# PAL3579.net
KiCad netlist of a schematic drawn in EAGLE
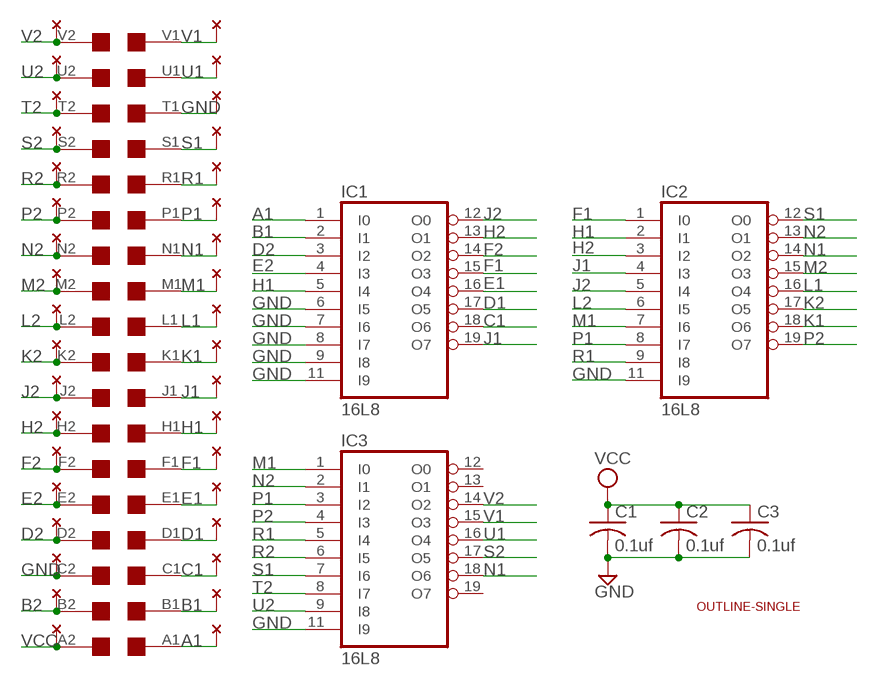
[diagram p0: schematic, sheet 1]

(export (version "E")
  (design (tool "Eeschema 10.0.6"))
  (components
    (comp (ref "C1")
      (value "0.1uf")
      (footprint "eagle-import:C050-025X075")
      (libsource (lib "eagle-import") (part "C-US050-025X075"))
    )
    (comp (ref "C2")
      (value "0.1uf")
      (footprint "eagle-import:C050-025X075")
      (libsource (lib "eagle-import") (part "C-US050-025X075"))
    )
    (comp (ref "C3")
      (value "0.1uf")
      (footprint "eagle-import:C050-025X075")
      (libsource (lib "eagle-import") (part "C-US050-025X075"))
    )
    (comp (ref "IC1")
      (value "16L8")
      (footprint "eagle-import:DIL20")
      (fields (field (name "MF") "TEXAS INSTRUMENTS") (field (name "MPN") "TIBPAL16L8-7CN"))
      (libsource (lib "eagle-import") (part "16L8"))
    )
    (comp (ref "IC2")
      (value "16L8")
      (footprint "eagle-import:DIL20")
      (fields (field (name "MF") "TEXAS INSTRUMENTS") (field (name "MPN") "TIBPAL16L8-7CN"))
      (libsource (lib "eagle-import") (part "16L8"))
    )
    (comp (ref "IC3")
      (value "16L8")
      (footprint "eagle-import:DIL20")
      (fields (field (name "MF") "TEXAS INSTRUMENTS") (field (name "MPN") "TIBPAL16L8-7CN"))
      (libsource (lib "eagle-import") (part "16L8"))
    )
    (comp (ref "U$1")
      (value "EDGE-2CONNECTOR")
      (footprint "eagle-import:EDGE-CON2")
      (libsource (lib "eagle-import") (part "EDGE-2CONNECTOR"))
    )
    (comp (ref "U$2")
      (value "OUTLINE-SINGLE")
      (footprint "eagle-import:SINGLE")
      (libsource (lib "eagle-import") (part "OUTLINE-SINGLE"))
    )
    (comp (ref "U$4")
      (value "THRU-HOLE2A")
      (footprint "eagle-import:THRU-HOLEA")
      (libsource (lib "eagle-import") (part "THRU-HOLE2A"))
    )
  )
  (nets
    (net (code "1") (name "/A1") (class "Default")
      (node (ref "IC1") (pin "1") (pinfunction "I0_1") (pintype "input"))
      (node (ref "U$1") (pin "A1") (pinfunction "1_A1") (pintype "bidirectional"))
      (node (ref "U$4") (pin "A1") (pinfunction "P$1_A1") (pintype "passive"))
    )
    (net (code "2") (name "/B1") (class "Default")
      (node (ref "IC1") (pin "2") (pinfunction "I1_2") (pintype "input"))
      (node (ref "U$1") (pin "B1") (pinfunction "1_B1") (pintype "bidirectional"))
      (node (ref "U$4") (pin "B1") (pinfunction "P$1_B1") (pintype "passive"))
    )
    (net (code "3") (name "/B2") (class "Default")
      (node (ref "U$1") (pin "B2") (pinfunction "1_B2") (pintype "bidirectional"))
      (node (ref "U$4") (pin "B2") (pinfunction "P$1_B2") (pintype "passive"))
    )
    (net (code "4") (name "/C1") (class "Default")
      (node (ref "IC1") (pin "18") (pinfunction "O6_18") (pintype "bidirectional"))
      (node (ref "U$1") (pin "C1") (pinfunction "1_C1") (pintype "bidirectional"))
      (node (ref "U$4") (pin "C1") (pinfunction "P$1_C1") (pintype "passive"))
    )
    (net (code "5") (name "/D1") (class "Default")
      (node (ref "IC1") (pin "17") (pinfunction "O5_17") (pintype "bidirectional"))
      (node (ref "U$1") (pin "D1") (pinfunction "1_D1") (pintype "bidirectional"))
      (node (ref "U$4") (pin "D1") (pinfunction "P$1_D1") (pintype "passive"))
    )
    (net (code "6") (name "/D2") (class "Default")
      (node (ref "IC1") (pin "3") (pinfunction "I2_3") (pintype "input"))
      (node (ref "U$1") (pin "D2") (pinfunction "1_D2") (pintype "bidirectional"))
      (node (ref "U$4") (pin "D2") (pinfunction "P$1_D2") (pintype "passive"))
    )
    (net (code "7") (name "/E1") (class "Default")
      (node (ref "IC1") (pin "16") (pinfunction "O4_16") (pintype "bidirectional"))
      (node (ref "U$1") (pin "E1") (pinfunction "1_E1") (pintype "bidirectional"))
      (node (ref "U$4") (pin "E1") (pinfunction "P$1_E1") (pintype "passive"))
    )
    (net (code "8") (name "/E2") (class "Default")
      (node (ref "IC1") (pin "4") (pinfunction "I3_4") (pintype "input"))
      (node (ref "U$1") (pin "E2") (pinfunction "1_E2") (pintype "bidirectional"))
      (node (ref "U$4") (pin "E2") (pinfunction "P$1_E2") (pintype "passive"))
    )
    (net (code "9") (name "/F1") (class "Default")
      (node (ref "IC1") (pin "15") (pinfunction "O3_15") (pintype "bidirectional"))
      (node (ref "IC2") (pin "1") (pinfunction "I0_1") (pintype "input"))
      (node (ref "U$1") (pin "F1") (pinfunction "1_F1") (pintype "bidirectional"))
      (node (ref "U$4") (pin "F1") (pinfunction "P$1_F1") (pintype "passive"))
    )
    (net (code "10") (name "/F2") (class "Default")
      (node (ref "IC1") (pin "14") (pinfunction "O2_14") (pintype "bidirectional"))
      (node (ref "U$1") (pin "F2") (pinfunction "1_F2") (pintype "bidirectional"))
      (node (ref "U$4") (pin "F2") (pinfunction "P$1_F2") (pintype "passive"))
    )
    (net (code "11") (name "/H1") (class "Default")
      (node (ref "IC1") (pin "5") (pinfunction "I4_5") (pintype "input"))
      (node (ref "IC2") (pin "2") (pinfunction "I1_2") (pintype "input"))
      (node (ref "U$1") (pin "H1") (pinfunction "1_H1") (pintype "bidirectional"))
      (node (ref "U$4") (pin "H1") (pinfunction "P$1_H1") (pintype "passive"))
    )
    (net (code "12") (name "/H2") (class "Default")
      (node (ref "IC1") (pin "13") (pinfunction "O1_13") (pintype "bidirectional"))
      (node (ref "IC2") (pin "3") (pinfunction "I2_3") (pintype "input"))
      (node (ref "U$1") (pin "H2") (pinfunction "1_H2") (pintype "bidirectional"))
      (node (ref "U$4") (pin "H2") (pinfunction "P$1_H2") (pintype "passive"))
    )
    (net (code "13") (name "/J1") (class "Default")
      (node (ref "IC1") (pin "19") (pinfunction "O7_19") (pintype "output"))
      (node (ref "IC2") (pin "4") (pinfunction "I3_4") (pintype "input"))
      (node (ref "U$1") (pin "J1") (pinfunction "1_J1") (pintype "bidirectional"))
      (node (ref "U$4") (pin "J1") (pinfunction "P$1_J1") (pintype "passive"))
    )
    (net (code "14") (name "/J2") (class "Default")
      (node (ref "IC1") (pin "12") (pinfunction "O0_12") (pintype "output"))
      (node (ref "IC2") (pin "5") (pinfunction "I4_5") (pintype "input"))
      (node (ref "U$1") (pin "J2") (pinfunction "1_J2") (pintype "bidirectional"))
      (node (ref "U$4") (pin "J2") (pinfunction "P$1_J2") (pintype "passive"))
    )
    (net (code "15") (name "/K1") (class "Default")
      (node (ref "IC2") (pin "18") (pinfunction "O6_18") (pintype "bidirectional"))
      (node (ref "U$1") (pin "K1") (pinfunction "1_K1") (pintype "bidirectional"))
      (node (ref "U$4") (pin "K1") (pinfunction "P$1_K1") (pintype "passive"))
    )
    (net (code "16") (name "/K2") (class "Default")
      (node (ref "IC2") (pin "17") (pinfunction "O5_17") (pintype "bidirectional"))
      (node (ref "U$1") (pin "K2") (pinfunction "1_K2") (pintype "bidirectional"))
      (node (ref "U$4") (pin "K2") (pinfunction "P$1_K2") (pintype "passive"))
    )
    (net (code "17") (name "/L1") (class "Default")
      (node (ref "IC2") (pin "16") (pinfunction "O4_16") (pintype "bidirectional"))
      (node (ref "U$1") (pin "L1") (pinfunction "1_L1") (pintype "bidirectional"))
      (node (ref "U$4") (pin "L1") (pinfunction "P$1_L1") (pintype "passive"))
    )
    (net (code "18") (name "/L2") (class "Default")
      (node (ref "IC2") (pin "6") (pinfunction "I5_6") (pintype "input"))
      (node (ref "U$1") (pin "L2") (pinfunction "1_L2") (pintype "bidirectional"))
      (node (ref "U$4") (pin "L2") (pinfunction "P$1_L2") (pintype "passive"))
    )
    (net (code "19") (name "/M1") (class "Default")
      (node (ref "IC2") (pin "7") (pinfunction "I6_7") (pintype "input"))
      (node (ref "IC3") (pin "1") (pinfunction "I0_1") (pintype "input"))
      (node (ref "U$1") (pin "M1") (pinfunction "1_M1") (pintype "bidirectional"))
      (node (ref "U$4") (pin "M1") (pinfunction "P$1_M1") (pintype "passive"))
    )
    (net (code "20") (name "/M2") (class "Default")
      (node (ref "IC2") (pin "15") (pinfunction "O3_15") (pintype "bidirectional"))
      (node (ref "U$1") (pin "M2") (pinfunction "1_M2") (pintype "bidirectional"))
      (node (ref "U$4") (pin "M2") (pinfunction "P$1_M2") (pintype "passive"))
    )
    (net (code "21") (name "/N1") (class "Default")
      (node (ref "IC2") (pin "14") (pinfunction "O2_14") (pintype "bidirectional"))
      (node (ref "IC3") (pin "18") (pinfunction "O6_18") (pintype "bidirectional"))
      (node (ref "U$1") (pin "N1") (pinfunction "1_N1") (pintype "bidirectional"))
      (node (ref "U$4") (pin "N1") (pinfunction "P$1_N1") (pintype "passive"))
    )
    (net (code "22") (name "/N2") (class "Default")
      (node (ref "IC2") (pin "13") (pinfunction "O1_13") (pintype "bidirectional"))
      (node (ref "IC3") (pin "2") (pinfunction "I1_2") (pintype "input"))
      (node (ref "U$1") (pin "N2") (pinfunction "1_N2") (pintype "bidirectional"))
      (node (ref "U$4") (pin "N2") (pinfunction "P$1_N2") (pintype "passive"))
    )
    (net (code "23") (name "/P1") (class "Default")
      (node (ref "IC2") (pin "8") (pinfunction "I7_8") (pintype "input"))
      (node (ref "IC3") (pin "3") (pinfunction "I2_3") (pintype "input"))
      (node (ref "U$1") (pin "P1") (pinfunction "1_P1") (pintype "bidirectional"))
      (node (ref "U$4") (pin "P1") (pinfunction "P$1_P1") (pintype "passive"))
    )
    (net (code "24") (name "/P2") (class "Default")
      (node (ref "IC2") (pin "19") (pinfunction "O7_19") (pintype "output"))
      (node (ref "IC3") (pin "4") (pinfunction "I3_4") (pintype "input"))
      (node (ref "U$1") (pin "P2") (pinfunction "1_P2") (pintype "bidirectional"))
      (node (ref "U$4") (pin "P2") (pinfunction "P$1_P2") (pintype "passive"))
    )
    (net (code "25") (name "/R1") (class "Default")
      (node (ref "IC2") (pin "9") (pinfunction "I8_9") (pintype "input"))
      (node (ref "IC3") (pin "5") (pinfunction "I4_5") (pintype "input"))
      (node (ref "U$1") (pin "R1") (pinfunction "1_R1") (pintype "bidirectional"))
      (node (ref "U$4") (pin "R1") (pinfunction "P$1_R1") (pintype "passive"))
    )
    (net (code "26") (name "/R2") (class "Default")
      (node (ref "IC3") (pin "6") (pinfunction "I5_6") (pintype "input"))
      (node (ref "U$1") (pin "R2") (pinfunction "1_R2") (pintype "bidirectional"))
      (node (ref "U$4") (pin "R2") (pinfunction "P$1_R2") (pintype "passive"))
    )
    (net (code "27") (name "/S1") (class "Default")
      (node (ref "IC2") (pin "12") (pinfunction "O0_12") (pintype "output"))
      (node (ref "IC3") (pin "7") (pinfunction "I6_7") (pintype "input"))
      (node (ref "U$1") (pin "S1") (pinfunction "1_S1") (pintype "bidirectional"))
      (node (ref "U$4") (pin "S1") (pinfunction "P$1_S1") (pintype "passive"))
    )
    (net (code "28") (name "/S2") (class "Default")
      (node (ref "IC3") (pin "17") (pinfunction "O5_17") (pintype "bidirectional"))
      (node (ref "U$1") (pin "S2") (pinfunction "1_S2") (pintype "bidirectional"))
      (node (ref "U$4") (pin "S2") (pinfunction "P$1_S2") (pintype "passive"))
    )
    (net (code "29") (name "/T2") (class "Default")
      (node (ref "IC3") (pin "8") (pinfunction "I7_8") (pintype "input"))
      (node (ref "U$1") (pin "T2") (pinfunction "1_T2") (pintype "bidirectional"))
      (node (ref "U$4") (pin "T2") (pinfunction "P$1_T2") (pintype "passive"))
    )
    (net (code "30") (name "/U1") (class "Default")
      (node (ref "IC3") (pin "16") (pinfunction "O4_16") (pintype "bidirectional"))
      (node (ref "U$1") (pin "U1") (pinfunction "1_U1") (pintype "bidirectional"))
      (node (ref "U$4") (pin "U1") (pinfunction "P$1_U1") (pintype "passive"))
    )
    (net (code "31") (name "/U2") (class "Default")
      (node (ref "IC3") (pin "9") (pinfunction "I8_9") (pintype "input"))
      (node (ref "U$1") (pin "U2") (pinfunction "1_U2") (pintype "bidirectional"))
      (node (ref "U$4") (pin "U2") (pinfunction "P$1_U2") (pintype "passive"))
    )
    (net (code "32") (name "/V1") (class "Default")
      (node (ref "IC3") (pin "15") (pinfunction "O3_15") (pintype "bidirectional"))
      (node (ref "U$1") (pin "V1") (pinfunction "1_V1") (pintype "bidirectional"))
      (node (ref "U$4") (pin "V1") (pinfunction "P$1_V1") (pintype "passive"))
    )
    (net (code "33") (name "/V2") (class "Default")
      (node (ref "IC3") (pin "14") (pinfunction "O2_14") (pintype "bidirectional"))
      (node (ref "U$1") (pin "V2") (pinfunction "1_V2") (pintype "bidirectional"))
      (node (ref "U$4") (pin "V2") (pinfunction "P$1_V2") (pintype "passive"))
    )
    (net (code "34") (name "GND") (class "Default")
      (node (ref "C1") (pin "2") (pinfunction "2_2") (pintype "passive"))
      (node (ref "C2") (pin "2") (pinfunction "2_2") (pintype "passive"))
      (node (ref "C3") (pin "2") (pinfunction "2_2") (pintype "passive"))
      (node (ref "IC1") (pin "11") (pinfunction "I9_11") (pintype "input"))
      (node (ref "IC1") (pin "6") (pinfunction "I5_6") (pintype "input"))
      (node (ref "IC1") (pin "7") (pinfunction "I6_7") (pintype "input"))
      (node (ref "IC1") (pin "8") (pinfunction "I7_8") (pintype "input"))
      (node (ref "IC1") (pin "9") (pinfunction "I8_9") (pintype "input"))
      (node (ref "IC2") (pin "11") (pinfunction "I9_11") (pintype "input"))
      (node (ref "IC3") (pin "11") (pinfunction "I9_11") (pintype "input"))
      (node (ref "U$1") (pin "C2") (pinfunction "1_C2") (pintype "bidirectional"))
      (node (ref "U$1") (pin "T1") (pinfunction "1_T1") (pintype "bidirectional"))
      (node (ref "U$4") (pin "C2") (pinfunction "P$1_C2") (pintype "passive"))
      (node (ref "U$4") (pin "T1") (pinfunction "P$1_T1") (pintype "passive"))
    )
    (net (code "35") (name "VCC") (class "Default")
      (node (ref "C1") (pin "1") (pinfunction "1_1") (pintype "passive"))
      (node (ref "C2") (pin "1") (pinfunction "1_1") (pintype "passive"))
      (node (ref "C3") (pin "1") (pinfunction "1_1") (pintype "passive"))
      (node (ref "U$1") (pin "A2") (pinfunction "1_A2") (pintype "bidirectional"))
      (node (ref "U$4") (pin "A2") (pinfunction "P$1_A2") (pintype "passive"))
    )
    (net (code "36") (name "unconnected-(IC3A-O0-Pad12)") (class "Default")
      (node (ref "IC3") (pin "12") (pinfunction "O0_12") (pintype "output"))
    )
    (net (code "37") (name "unconnected-(IC3A-O1-Pad13)") (class "Default")
      (node (ref "IC3") (pin "13") (pinfunction "O1_13") (pintype "bidirectional"))
    )
    (net (code "38") (name "unconnected-(IC3A-O7-Pad19)") (class "Default")
      (node (ref "IC3") (pin "19") (pinfunction "O7_19") (pintype "output"))
    )
  )
)
